# ugv_board.net
KiCad netlist of a schematic drawn in EAGLE
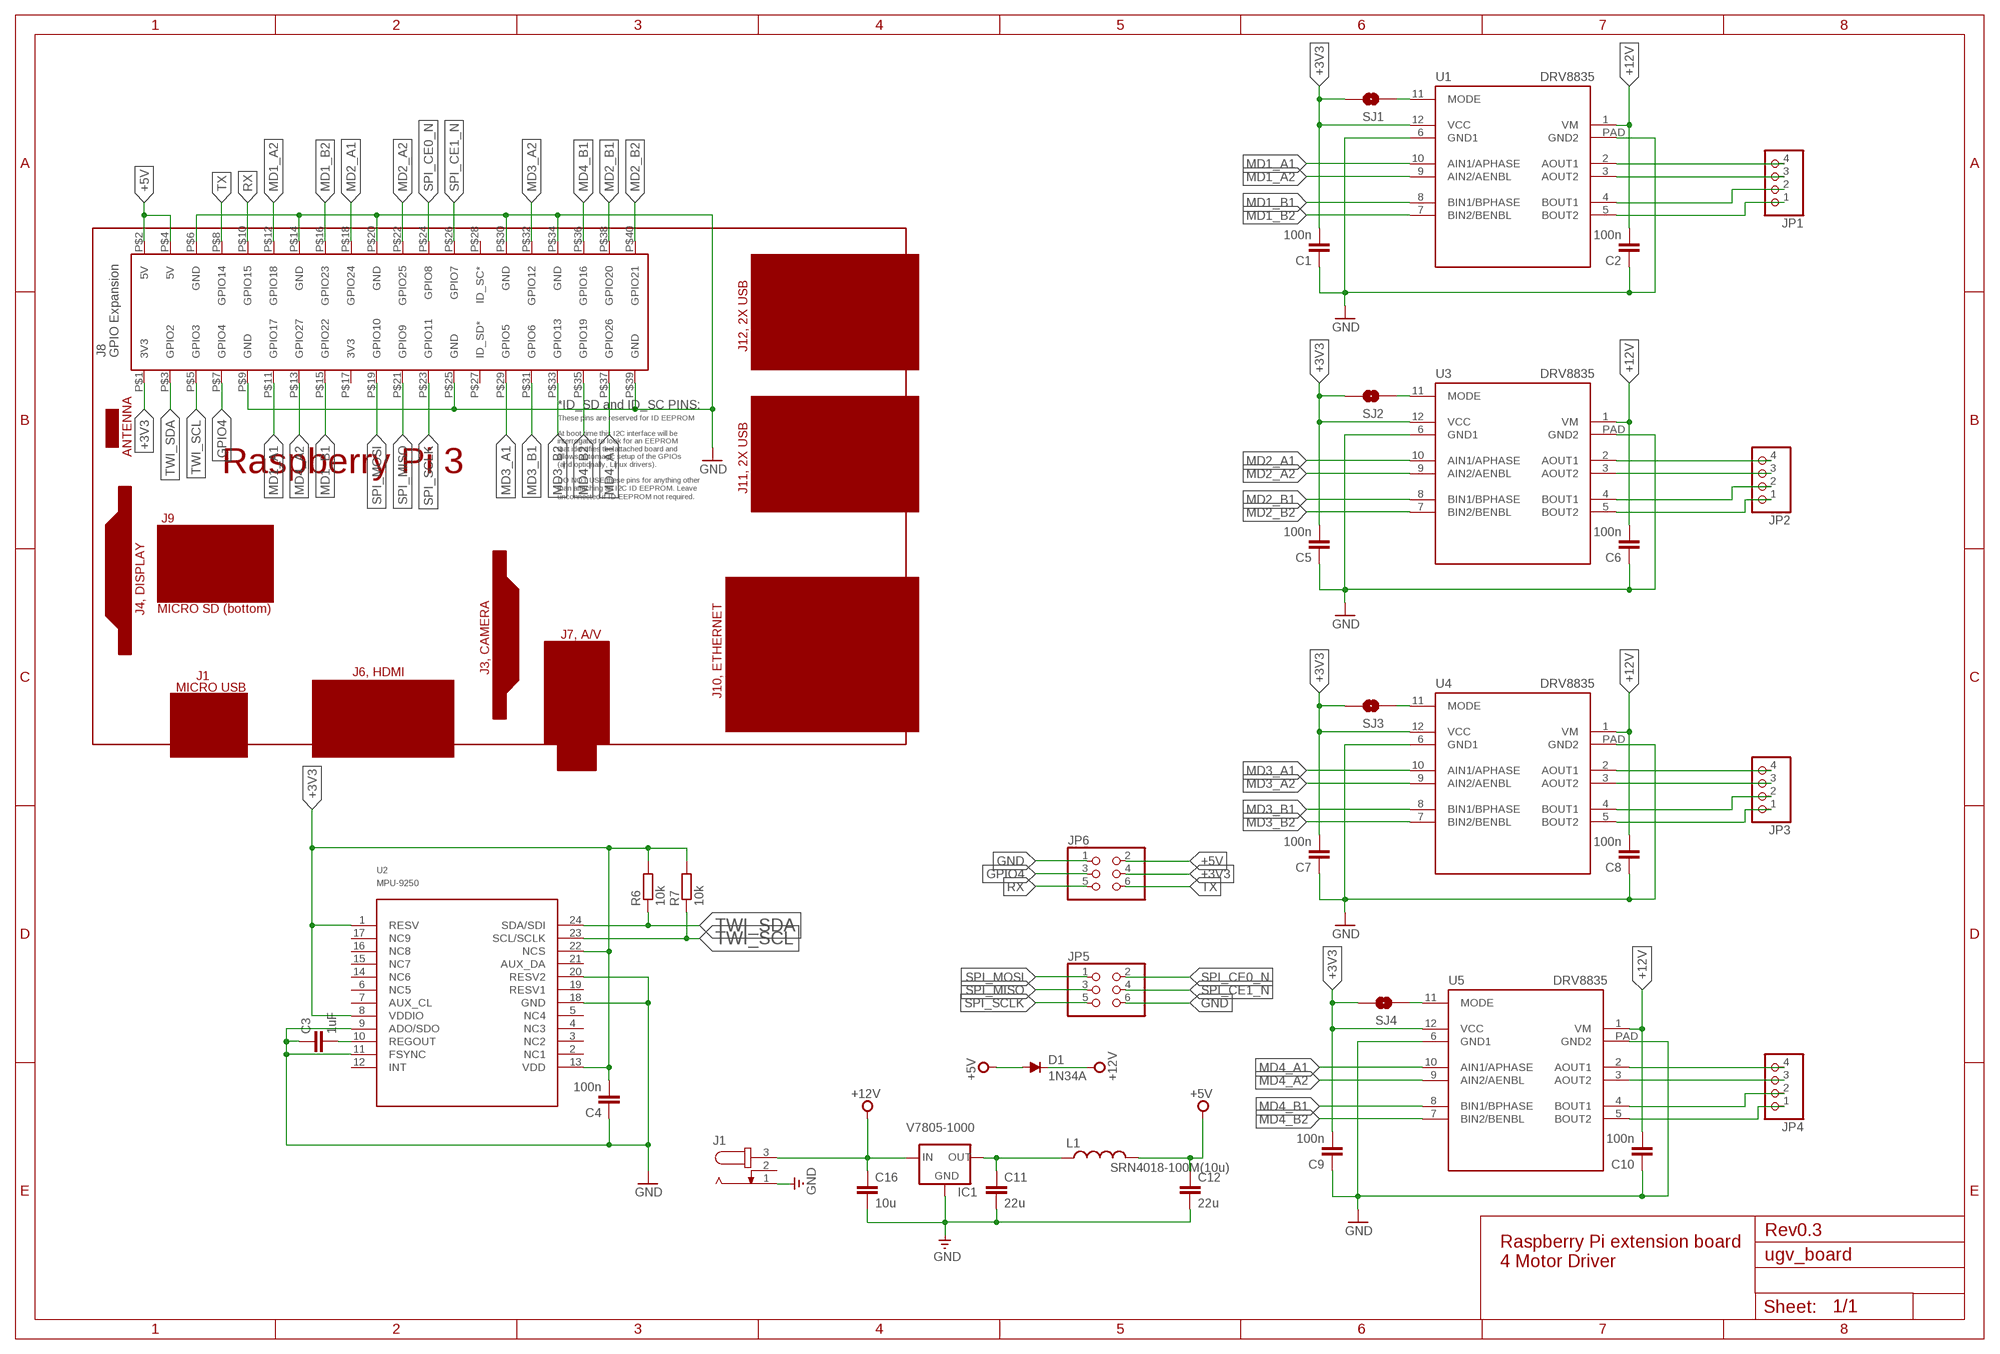
[diagram p0: schematic, sheet 1]

(export (version "E")
  (design (tool "Eeschema 10.0.6"))
  (components
    (comp (ref "C1")
      (value "100n")
      (footprint "eagle-import:C0402")
      (libsource (lib "eagle-import") (part "resistor_348_C-EUC0402"))
    )
    (comp (ref "C2")
      (value "100n")
      (footprint "eagle-import:C0402")
      (libsource (lib "eagle-import") (part "resistor_348_C-EUC0402"))
    )
    (comp (ref "C3")
      (value "1uF")
      (footprint "eagle-import:C0402")
      (libsource (lib "eagle-import") (part "resistor_348_C-EUC0402"))
    )
    (comp (ref "C4")
      (value "100n")
      (footprint "eagle-import:C0402")
      (libsource (lib "eagle-import") (part "resistor_348_C-EUC0402"))
    )
    (comp (ref "C5")
      (value "100n")
      (footprint "eagle-import:C0402")
      (libsource (lib "eagle-import") (part "resistor_348_C-EUC0402"))
    )
    (comp (ref "C6")
      (value "100n")
      (footprint "eagle-import:C0402")
      (libsource (lib "eagle-import") (part "resistor_348_C-EUC0402"))
    )
    (comp (ref "C7")
      (value "100n")
      (footprint "eagle-import:C0402")
      (libsource (lib "eagle-import") (part "resistor_348_C-EUC0402"))
    )
    (comp (ref "C8")
      (value "100n")
      (footprint "eagle-import:C0402")
      (libsource (lib "eagle-import") (part "resistor_348_C-EUC0402"))
    )
    (comp (ref "C9")
      (value "100n")
      (footprint "eagle-import:C0402")
      (libsource (lib "eagle-import") (part "resistor_348_C-EUC0402"))
    )
    (comp (ref "C10")
      (value "100n")
      (footprint "eagle-import:C0402")
      (libsource (lib "eagle-import") (part "resistor_348_C-EUC0402"))
    )
    (comp (ref "C11")
      (value "22u")
      (footprint "eagle-import:C0603")
      (libsource (lib "eagle-import") (part "C-EUC0603"))
    )
    (comp (ref "C12")
      (value "22u")
      (footprint "eagle-import:C0603")
      (libsource (lib "eagle-import") (part "C-EUC0603"))
    )
    (comp (ref "C16")
      (value "10u")
      (footprint "eagle-import:C0603")
      (libsource (lib "eagle-import") (part "C-EUC0603"))
    )
    (comp (ref "D1")
      (value "1N34A")
      (footprint "eagle-import:DO07")
      (libsource (lib "eagle-import") (part "1N34A"))
    )
    (comp (ref "IC1")
      (value "V7805-1000")
      (footprint "eagle-import:DIP_3PIN")
      (libsource (lib "eagle-import") (part "VR_1OUTXX"))
    )
    (comp (ref "J1")
      (value "JACK-PLUG0")
      (footprint "eagle-import:SPC4077")
      (libsource (lib "eagle-import") (part "JACK-PLUG0"))
    )
    (comp (ref "JP1")
      (value "PINHD-1X4M")
      (footprint "eagle-import:1X04M")
      (libsource (lib "eagle-import") (part "PINHD-1X4M"))
    )
    (comp (ref "JP2")
      (value "PINHD-1X4M")
      (footprint "eagle-import:1X04M")
      (libsource (lib "eagle-import") (part "PINHD-1X4M"))
    )
    (comp (ref "JP3")
      (value "PINHD-1X4M")
      (footprint "eagle-import:1X04M")
      (libsource (lib "eagle-import") (part "PINHD-1X4M"))
    )
    (comp (ref "JP4")
      (value "PINHD-1X4M")
      (footprint "eagle-import:1X04M")
      (libsource (lib "eagle-import") (part "PINHD-1X4M"))
    )
    (comp (ref "JP5")
      (value "PINHD-2X3")
      (footprint "eagle-import:2X03")
      (libsource (lib "eagle-import") (part "PINHD-2X3"))
    )
    (comp (ref "JP6")
      (value "PINHD-2X3")
      (footprint "eagle-import:2X03")
      (libsource (lib "eagle-import") (part "PINHD-2X3"))
    )
    (comp (ref "L1")
      (value "SRN4018-100M(10u)")
      (footprint "eagle-import:BOURNS-SRN4018")
      (libsource (lib "eagle-import") (part "BOURNS-SRN4018"))
    )
    (comp (ref "PCB1")
      (value "RPI3")
      (footprint "eagle-import:RPI3")
      (libsource (lib "eagle-import") (part "RPI3"))
    )
    (comp (ref "R6")
      (value "10k")
      (footprint "eagle-import:R0402")
      (libsource (lib "eagle-import") (part "R-EU_R0402"))
    )
    (comp (ref "R7")
      (value "10k")
      (footprint "eagle-import:R0402")
      (libsource (lib "eagle-import") (part "R-EU_R0402"))
    )
    (comp (ref "SJ1")
      (value "SOLDERJUMPERNC")
      (footprint "eagle-import:SJ_2S")
      (libsource (lib "eagle-import") (part "SOLDERJUMPERNC"))
    )
    (comp (ref "SJ2")
      (value "SOLDERJUMPERNC")
      (footprint "eagle-import:SJ_2S")
      (libsource (lib "eagle-import") (part "SOLDERJUMPERNC"))
    )
    (comp (ref "SJ3")
      (value "SOLDERJUMPERNC")
      (footprint "eagle-import:SJ_2S")
      (libsource (lib "eagle-import") (part "SOLDERJUMPERNC"))
    )
    (comp (ref "SJ4")
      (value "SOLDERJUMPERNC")
      (footprint "eagle-import:SJ_2S")
      (libsource (lib "eagle-import") (part "SOLDERJUMPERNC"))
    )
    (comp (ref "U1")
      (value "DRV8835")
      (footprint "eagle-import:WSON_2X3")
      (libsource (lib "eagle-import") (part "DRV8835"))
    )
    (comp (ref "U2")
      (value "MPU-9250")
      (footprint "eagle-import:LEAD-QFN24")
      (libsource (lib "eagle-import") (part "MPU-9250"))
    )
    (comp (ref "U3")
      (value "DRV8835")
      (footprint "eagle-import:WSON_2X3")
      (libsource (lib "eagle-import") (part "DRV8835"))
    )
    (comp (ref "U4")
      (value "DRV8835")
      (footprint "eagle-import:WSON_2X3")
      (libsource (lib "eagle-import") (part "DRV8835"))
    )
    (comp (ref "U5")
      (value "DRV8835")
      (footprint "eagle-import:WSON_2X3")
      (libsource (lib "eagle-import") (part "DRV8835"))
    )
  )
  (nets
    (net (code "1") (name "+3V3") (class "Default")
      (node (ref "C1") (pin "2") (pinfunction "2_2") (pintype "passive"))
      (node (ref "C4") (pin "2") (pinfunction "2_2") (pintype "passive"))
      (node (ref "C5") (pin "2") (pinfunction "2_2") (pintype "passive"))
      (node (ref "C7") (pin "2") (pinfunction "2_2") (pintype "passive"))
      (node (ref "C9") (pin "2") (pinfunction "2_2") (pintype "passive"))
      (node (ref "JP6") (pin "4") (pinfunction "4_4") (pintype "passive"))
      (node (ref "PCB1") (pin "P$1") (pinfunction "3V3_P$1") (pintype "bidirectional"))
      (node (ref "R6") (pin "2") (pinfunction "2_2") (pintype "passive"))
      (node (ref "R7") (pin "2") (pinfunction "2_2") (pintype "passive"))
      (node (ref "SJ1") (pin "2") (pinfunction "2_2") (pintype "passive"))
      (node (ref "SJ2") (pin "2") (pinfunction "2_2") (pintype "passive"))
      (node (ref "SJ3") (pin "2") (pinfunction "2_2") (pintype "passive"))
      (node (ref "SJ4") (pin "2") (pinfunction "2_2") (pintype "passive"))
      (node (ref "U1") (pin "12") (pinfunction "VCC_12") (pintype "bidirectional"))
      (node (ref "U2") (pin "1") (pinfunction "RESV_1") (pintype "bidirectional"))
      (node (ref "U2") (pin "13") (pinfunction "VDD_13") (pintype "bidirectional"))
      (node (ref "U2") (pin "22") (pinfunction "NCS_22") (pintype "bidirectional"))
      (node (ref "U2") (pin "8") (pinfunction "VDDIO_8") (pintype "bidirectional"))
      (node (ref "U3") (pin "12") (pinfunction "VCC_12") (pintype "bidirectional"))
      (node (ref "U4") (pin "12") (pinfunction "VCC_12") (pintype "bidirectional"))
      (node (ref "U5") (pin "12") (pinfunction "VCC_12") (pintype "bidirectional"))
    )
    (net (code "2") (name "+5V") (class "Default")
      (node (ref "C12") (pin "1") (pinfunction "1_1") (pintype "passive"))
      (node (ref "D1") (pin "A") (pinfunction "A_A") (pintype "passive"))
      (node (ref "JP6") (pin "2") (pinfunction "2_2") (pintype "passive"))
      (node (ref "L1") (pin "P$1") (pinfunction "1_P$1") (pintype "passive"))
      (node (ref "PCB1") (pin "P$2") (pinfunction "5V_P$2") (pintype "bidirectional"))
      (node (ref "PCB1") (pin "P$4") (pinfunction "5V_P$4") (pintype "bidirectional"))
    )
    (net (code "3") (name "+12V") (class "Default")
      (node (ref "C10") (pin "2") (pinfunction "2_2") (pintype "passive"))
      (node (ref "C16") (pin "1") (pinfunction "1_1") (pintype "passive"))
      (node (ref "C2") (pin "2") (pinfunction "2_2") (pintype "passive"))
      (node (ref "C6") (pin "2") (pinfunction "2_2") (pintype "passive"))
      (node (ref "C8") (pin "2") (pinfunction "2_2") (pintype "passive"))
      (node (ref "D1") (pin "C") (pinfunction "C_C") (pintype "passive"))
      (node (ref "IC1") (pin "IN") (pinfunction "IN_IN") (pintype "input"))
      (node (ref "J1") (pin "3") (pinfunction "3_3") (pintype "passive"))
      (node (ref "U1") (pin "1") (pinfunction "VM_1") (pintype "bidirectional"))
      (node (ref "U3") (pin "1") (pinfunction "VM_1") (pintype "bidirectional"))
      (node (ref "U4") (pin "1") (pinfunction "VM_1") (pintype "bidirectional"))
      (node (ref "U5") (pin "1") (pinfunction "VM_1") (pintype "bidirectional"))
    )
    (net (code "4") (name "GND") (class "Default")
      (node (ref "C1") (pin "1") (pinfunction "1_1") (pintype "passive"))
      (node (ref "C10") (pin "1") (pinfunction "1_1") (pintype "passive"))
      (node (ref "C11") (pin "2") (pinfunction "2_2") (pintype "passive"))
      (node (ref "C12") (pin "2") (pinfunction "2_2") (pintype "passive"))
      (node (ref "C16") (pin "2") (pinfunction "2_2") (pintype "passive"))
      (node (ref "C2") (pin "1") (pinfunction "1_1") (pintype "passive"))
      (node (ref "C3") (pin "1") (pinfunction "1_1") (pintype "passive"))
      (node (ref "C4") (pin "1") (pinfunction "1_1") (pintype "passive"))
      (node (ref "C5") (pin "1") (pinfunction "1_1") (pintype "passive"))
      (node (ref "C6") (pin "1") (pinfunction "1_1") (pintype "passive"))
      (node (ref "C7") (pin "1") (pinfunction "1_1") (pintype "passive"))
      (node (ref "C8") (pin "1") (pinfunction "1_1") (pintype "passive"))
      (node (ref "C9") (pin "1") (pinfunction "1_1") (pintype "passive"))
      (node (ref "IC1") (pin "GND") (pinfunction "GND_GND") (pintype "input"))
      (node (ref "J1") (pin "1") (pinfunction "1_1") (pintype "passive"))
      (node (ref "JP5") (pin "6") (pinfunction "6_6") (pintype "passive"))
      (node (ref "JP6") (pin "1") (pinfunction "1_1") (pintype "passive"))
      (node (ref "PCB1") (pin "P$14") (pinfunction "GND_P$14") (pintype "bidirectional"))
      (node (ref "PCB1") (pin "P$20") (pinfunction "GND_P$20") (pintype "bidirectional"))
      (node (ref "PCB1") (pin "P$25") (pinfunction "GND_P$25") (pintype "bidirectional"))
      (node (ref "PCB1") (pin "P$30") (pinfunction "GND_P$30") (pintype "bidirectional"))
      (node (ref "PCB1") (pin "P$34") (pinfunction "GND_P$34") (pintype "bidirectional"))
      (node (ref "PCB1") (pin "P$39") (pinfunction "GND_P$39") (pintype "bidirectional"))
      (node (ref "PCB1") (pin "P$6") (pinfunction "GND_P$6") (pintype "bidirectional"))
      (node (ref "PCB1") (pin "P$9") (pinfunction "GND_P$9") (pintype "bidirectional"))
      (node (ref "U1") (pin "6") (pinfunction "GND1_6") (pintype "bidirectional"))
      (node (ref "U1") (pin "PAD") (pinfunction "GND2_PAD") (pintype "bidirectional"))
      (node (ref "U2") (pin "11") (pinfunction "FSYNC_11") (pintype "bidirectional"))
      (node (ref "U2") (pin "18") (pinfunction "GND_18") (pintype "bidirectional"))
      (node (ref "U2") (pin "20") (pinfunction "RESV2_20") (pintype "bidirectional"))
      (node (ref "U2") (pin "9") (pinfunction "ADO/SDO_9") (pintype "bidirectional"))
      (node (ref "U3") (pin "6") (pinfunction "GND1_6") (pintype "bidirectional"))
      (node (ref "U3") (pin "PAD") (pinfunction "GND2_PAD") (pintype "bidirectional"))
      (node (ref "U4") (pin "6") (pinfunction "GND1_6") (pintype "bidirectional"))
      (node (ref "U4") (pin "PAD") (pinfunction "GND2_PAD") (pintype "bidirectional"))
      (node (ref "U5") (pin "6") (pinfunction "GND1_6") (pintype "bidirectional"))
      (node (ref "U5") (pin "PAD") (pinfunction "GND2_PAD") (pintype "bidirectional"))
    )
    (net (code "5") (name "GPIO4") (class "Default")
      (node (ref "JP6") (pin "3") (pinfunction "3_3") (pintype "passive"))
      (node (ref "PCB1") (pin "P$7") (pinfunction "GPIO4_P$7") (pintype "bidirectional"))
    )
    (net (code "6") (name "MD1_A1") (class "Default")
      (node (ref "PCB1") (pin "P$11") (pinfunction "GPIO17_P$11") (pintype "bidirectional"))
      (node (ref "U1") (pin "10") (pinfunction "AIN1/APHASE_10") (pintype "bidirectional"))
    )
    (net (code "7") (name "MD1_A2") (class "Default")
      (node (ref "PCB1") (pin "P$12") (pinfunction "GPIO18_P$12") (pintype "bidirectional"))
      (node (ref "U1") (pin "9") (pinfunction "AIN2/AENBL_9") (pintype "bidirectional"))
    )
    (net (code "8") (name "MD1_B1") (class "Default")
      (node (ref "PCB1") (pin "P$15") (pinfunction "GPIO22_P$15") (pintype "bidirectional"))
      (node (ref "U1") (pin "8") (pinfunction "BIN1/BPHASE_8") (pintype "bidirectional"))
    )
    (net (code "9") (name "MD1_B2") (class "Default")
      (node (ref "PCB1") (pin "P$16") (pinfunction "GPIO23_P$16") (pintype "bidirectional"))
      (node (ref "U1") (pin "7") (pinfunction "BIN2/BENBL_7") (pintype "bidirectional"))
    )
    (net (code "10") (name "MD2_A1") (class "Default")
      (node (ref "PCB1") (pin "P$18") (pinfunction "GPIO24_P$18") (pintype "bidirectional"))
      (node (ref "U3") (pin "10") (pinfunction "AIN1/APHASE_10") (pintype "bidirectional"))
    )
    (net (code "11") (name "MD2_A2") (class "Default")
      (node (ref "PCB1") (pin "P$22") (pinfunction "GPIO25_P$22") (pintype "bidirectional"))
      (node (ref "U3") (pin "9") (pinfunction "AIN2/AENBL_9") (pintype "bidirectional"))
    )
    (net (code "12") (name "MD2_B1") (class "Default")
      (node (ref "PCB1") (pin "P$38") (pinfunction "GPIO20_P$38") (pintype "bidirectional"))
      (node (ref "U3") (pin "8") (pinfunction "BIN1/BPHASE_8") (pintype "bidirectional"))
    )
    (net (code "13") (name "MD2_B2") (class "Default")
      (node (ref "PCB1") (pin "P$40") (pinfunction "GPIO21_P$40") (pintype "bidirectional"))
      (node (ref "U3") (pin "7") (pinfunction "BIN2/BENBL_7") (pintype "bidirectional"))
    )
    (net (code "14") (name "MD3_A1") (class "Default")
      (node (ref "PCB1") (pin "P$29") (pinfunction "GPIO5_P$29") (pintype "bidirectional"))
      (node (ref "U4") (pin "10") (pinfunction "AIN1/APHASE_10") (pintype "bidirectional"))
    )
    (net (code "15") (name "MD3_A2") (class "Default")
      (node (ref "PCB1") (pin "P$32") (pinfunction "GPIO12_P$32") (pintype "bidirectional"))
      (node (ref "U4") (pin "9") (pinfunction "AIN2/AENBL_9") (pintype "bidirectional"))
    )
    (net (code "16") (name "MD3_B1") (class "Default")
      (node (ref "PCB1") (pin "P$31") (pinfunction "GPIO6_P$31") (pintype "bidirectional"))
      (node (ref "U4") (pin "8") (pinfunction "BIN1/BPHASE_8") (pintype "bidirectional"))
    )
    (net (code "17") (name "MD3_B2") (class "Default")
      (node (ref "PCB1") (pin "P$33") (pinfunction "GPIO13_P$33") (pintype "bidirectional"))
      (node (ref "U4") (pin "7") (pinfunction "BIN2/BENBL_7") (pintype "bidirectional"))
    )
    (net (code "18") (name "MD4_A1") (class "Default")
      (node (ref "PCB1") (pin "P$37") (pinfunction "GPIO26_P$37") (pintype "bidirectional"))
      (node (ref "U5") (pin "10") (pinfunction "AIN1/APHASE_10") (pintype "bidirectional"))
    )
    (net (code "19") (name "MD4_A2") (class "Default")
      (node (ref "PCB1") (pin "P$13") (pinfunction "GPIO27_P$13") (pintype "bidirectional"))
      (node (ref "U5") (pin "9") (pinfunction "AIN2/AENBL_9") (pintype "bidirectional"))
    )
    (net (code "20") (name "MD4_B1") (class "Default")
      (node (ref "PCB1") (pin "P$36") (pinfunction "GPIO16_P$36") (pintype "bidirectional"))
      (node (ref "U5") (pin "8") (pinfunction "BIN1/BPHASE_8") (pintype "bidirectional"))
    )
    (net (code "21") (name "MD4_B2") (class "Default")
      (node (ref "PCB1") (pin "P$35") (pinfunction "GPIO19_P$35") (pintype "bidirectional"))
      (node (ref "U5") (pin "7") (pinfunction "BIN2/BENBL_7") (pintype "bidirectional"))
    )
    (net (code "22") (name "Net-(L1-2)") (class "Default")
      (node (ref "C11") (pin "1") (pinfunction "1_1") (pintype "passive"))
      (node (ref "IC1") (pin "OUT") (pinfunction "OUT_OUT") (pintype "passive"))
      (node (ref "L1") (pin "P$2") (pinfunction "2_P$2") (pintype "passive"))
    )
    (net (code "23") (name "Net-(U1-AOUT1)") (class "Default")
      (node (ref "JP1") (pin "4") (pinfunction "4_4") (pintype "passive"))
      (node (ref "U1") (pin "2") (pinfunction "AOUT1_2") (pintype "bidirectional"))
    )
    (net (code "24") (name "Net-(U1-AOUT2)") (class "Default")
      (node (ref "JP1") (pin "3") (pinfunction "3_3") (pintype "passive"))
      (node (ref "U1") (pin "3") (pinfunction "AOUT2_3") (pintype "bidirectional"))
    )
    (net (code "25") (name "Net-(U1-BOUT1)") (class "Default")
      (node (ref "JP1") (pin "2") (pinfunction "2_2") (pintype "passive"))
      (node (ref "U1") (pin "4") (pinfunction "BOUT1_4") (pintype "bidirectional"))
    )
    (net (code "26") (name "Net-(U1-BOUT2)") (class "Default")
      (node (ref "JP1") (pin "1") (pinfunction "1_1") (pintype "passive"))
      (node (ref "U1") (pin "5") (pinfunction "BOUT2_5") (pintype "bidirectional"))
    )
    (net (code "27") (name "Net-(U1-MODE)") (class "Default")
      (node (ref "SJ1") (pin "1") (pinfunction "1_1") (pintype "passive"))
      (node (ref "U1") (pin "11") (pinfunction "MODE_11") (pintype "bidirectional"))
    )
    (net (code "28") (name "Net-(U2-REGOUT)") (class "Default")
      (node (ref "C3") (pin "2") (pinfunction "2_2") (pintype "passive"))
      (node (ref "U2") (pin "10") (pinfunction "REGOUT_10") (pintype "bidirectional"))
    )
    (net (code "29") (name "Net-(U3-AOUT1)") (class "Default")
      (node (ref "JP2") (pin "4") (pinfunction "4_4") (pintype "passive"))
      (node (ref "U3") (pin "2") (pinfunction "AOUT1_2") (pintype "bidirectional"))
    )
    (net (code "30") (name "Net-(U3-AOUT2)") (class "Default")
      (node (ref "JP2") (pin "3") (pinfunction "3_3") (pintype "passive"))
      (node (ref "U3") (pin "3") (pinfunction "AOUT2_3") (pintype "bidirectional"))
    )
    (net (code "31") (name "Net-(U3-BOUT1)") (class "Default")
      (node (ref "JP2") (pin "2") (pinfunction "2_2") (pintype "passive"))
      (node (ref "U3") (pin "4") (pinfunction "BOUT1_4") (pintype "bidirectional"))
    )
    (net (code "32") (name "Net-(U3-BOUT2)") (class "Default")
      (node (ref "JP2") (pin "1") (pinfunction "1_1") (pintype "passive"))
      (node (ref "U3") (pin "5") (pinfunction "BOUT2_5") (pintype "bidirectional"))
    )
    (net (code "33") (name "Net-(U3-MODE)") (class "Default")
      (node (ref "SJ2") (pin "1") (pinfunction "1_1") (pintype "passive"))
      (node (ref "U3") (pin "11") (pinfunction "MODE_11") (pintype "bidirectional"))
    )
    (net (code "34") (name "Net-(U4-AOUT1)") (class "Default")
      (node (ref "JP3") (pin "4") (pinfunction "4_4") (pintype "passive"))
      (node (ref "U4") (pin "2") (pinfunction "AOUT1_2") (pintype "bidirectional"))
    )
    (net (code "35") (name "Net-(U4-AOUT2)") (class "Default")
      (node (ref "JP3") (pin "3") (pinfunction "3_3") (pintype "passive"))
      (node (ref "U4") (pin "3") (pinfunction "AOUT2_3") (pintype "bidirectional"))
    )
    (net (code "36") (name "Net-(U4-BOUT1)") (class "Default")
      (node (ref "JP3") (pin "2") (pinfunction "2_2") (pintype "passive"))
      (node (ref "U4") (pin "4") (pinfunction "BOUT1_4") (pintype "bidirectional"))
    )
    (net (code "37") (name "Net-(U4-BOUT2)") (class "Default")
      (node (ref "JP3") (pin "1") (pinfunction "1_1") (pintype "passive"))
      (node (ref "U4") (pin "5") (pinfunction "BOUT2_5") (pintype "bidirectional"))
    )
    (net (code "38") (name "Net-(U4-MODE)") (class "Default")
      (node (ref "SJ3") (pin "1") (pinfunction "1_1") (pintype "passive"))
      (node (ref "U4") (pin "11") (pinfunction "MODE_11") (pintype "bidirectional"))
    )
    (net (code "39") (name "Net-(U5-AOUT1)") (class "Default")
      (node (ref "JP4") (pin "4") (pinfunction "4_4") (pintype "passive"))
      (node (ref "U5") (pin "2") (pinfunction "AOUT1_2") (pintype "bidirectional"))
    )
    (net (code "40") (name "Net-(U5-AOUT2)") (class "Default")
      (node (ref "JP4") (pin "3") (pinfunction "3_3") (pintype "passive"))
      (node (ref "U5") (pin "3") (pinfunction "AOUT2_3") (pintype "bidirectional"))
    )
    (net (code "41") (name "Net-(U5-BOUT1)") (class "Default")
      (node (ref "JP4") (pin "2") (pinfunction "2_2") (pintype "passive"))
      (node (ref "U5") (pin "4") (pinfunction "BOUT1_4") (pintype "bidirectional"))
    )
    (net (code "42") (name "Net-(U5-BOUT2)") (class "Default")
      (node (ref "JP4") (pin "1") (pinfunction "1_1") (pintype "passive"))
      (node (ref "U5") (pin "5") (pinfunction "BOUT2_5") (pintype "bidirectional"))
    )
    (net (code "43") (name "Net-(U5-MODE)") (class "Default")
      (node (ref "SJ4") (pin "1") (pinfunction "1_1") (pintype "passive"))
      (node (ref "U5") (pin "11") (pinfunction "MODE_11") (pintype "bidirectional"))
    )
    (net (code "44") (name "RX") (class "Default")
      (node (ref "JP6") (pin "5") (pinfunction "5_5") (pintype "passive"))
      (node (ref "PCB1") (pin "P$10") (pinfunction "GPIO15_P$10") (pintype "bidirectional"))
    )
    (net (code "45") (name "SPI_CE0_N") (class "Default")
      (node (ref "JP5") (pin "2") (pinfunction "2_2") (pintype "passive"))
      (node (ref "PCB1") (pin "P$24") (pinfunction "GPIO8_P$24") (pintype "bidirectional"))
    )
    (net (code "46") (name "SPI_CE1_N") (class "Default")
      (node (ref "JP5") (pin "4") (pinfunction "4_4") (pintype "passive"))
      (node (ref "PCB1") (pin "P$26") (pinfunction "GPIO7_P$26") (pintype "bidirectional"))
    )
    (net (code "47") (name "SPI_MISO") (class "Default")
      (node (ref "JP5") (pin "3") (pinfunction "3_3") (pintype "passive"))
      (node (ref "PCB1") (pin "P$21") (pinfunction "GPIO9_P$21") (pintype "bidirectional"))
    )
    (net (code "48") (name "SPI_MOSI") (class "Default")
      (node (ref "JP5") (pin "1") (pinfunction "1_1") (pintype "passive"))
      (node (ref "PCB1") (pin "P$19") (pinfunction "GPIO10_P$19") (pintype "bidirectional"))
    )
    (net (code "49") (name "SPI_SCLK") (class "Default")
      (node (ref "JP5") (pin "5") (pinfunction "5_5") (pintype "passive"))
      (node (ref "PCB1") (pin "P$23") (pinfunction "GPIO11_P$23") (pintype "bidirectional"))
    )
    (net (code "50") (name "TWI_SCL") (class "Default")
      (node (ref "PCB1") (pin "P$5") (pinfunction "GPIO3_P$5") (pintype "bidirectional"))
      (node (ref "R7") (pin "1") (pinfunction "1_1") (pintype "passive"))
      (node (ref "U2") (pin "23") (pinfunction "SCL/SCLK_23") (pintype "bidirectional"))
    )
    (net (code "51") (name "TWI_SDA") (class "Default")
      (node (ref "PCB1") (pin "P$3") (pinfunction "GPIO2_P$3") (pintype "bidirectional"))
      (node (ref "R6") (pin "1") (pinfunction "1_1") (pintype "passive"))
      (node (ref "U2") (pin "24") (pinfunction "SDA/SDI_24") (pintype "bidirectional"))
    )
    (net (code "52") (name "TX") (class "Default")
      (node (ref "JP6") (pin "6") (pinfunction "6_6") (pintype "passive"))
      (node (ref "PCB1") (pin "P$8") (pinfunction "GPIO14_P$8") (pintype "bidirectional"))
    )
    (net (code "53") (name "unconnected-(J1-Pad2)") (class "Default")
      (node (ref "J1") (pin "2") (pinfunction "2_2") (pintype "passive"))
    )
    (net (code "54") (name "unconnected-(PCB1-3V3-PadP$17)") (class "Default")
      (node (ref "PCB1") (pin "P$17") (pinfunction "3V3_P$17") (pintype "bidirectional"))
    )
    (net (code "55") (name "unconnected-(PCB1-ID_SC*-PadP$28)") (class "Default")
      (node (ref "PCB1") (pin "P$28") (pinfunction "ID_SC*_P$28") (pintype "bidirectional"))
    )
    (net (code "56") (name "unconnected-(PCB1-ID_SD*-PadP$27)") (class "Default")
      (node (ref "PCB1") (pin "P$27") (pinfunction "ID_SD*_P$27") (pintype "bidirectional"))
    )
    (net (code "57") (name "unconnected-(U2-AUX_CL-Pad7)") (class "Default")
      (node (ref "U2") (pin "7") (pinfunction "AUX_CL_7") (pintype "bidirectional"))
    )
    (net (code "58") (name "unconnected-(U2-AUX_DA-Pad21)") (class "Default")
      (node (ref "U2") (pin "21") (pinfunction "AUX_DA_21") (pintype "bidirectional"))
    )
    (net (code "59") (name "unconnected-(U2-INT-Pad12)") (class "Default")
      (node (ref "U2") (pin "12") (pinfunction "INT_12") (pintype "bidirectional"))
    )
    (net (code "60") (name "unconnected-(U2-NC1-Pad2)") (class "Default")
      (node (ref "U2") (pin "2") (pinfunction "NC1_2") (pintype "bidirectional"))
    )
    (net (code "61") (name "unconnected-(U2-NC2-Pad3)") (class "Default")
      (node (ref "U2") (pin "3") (pinfunction "NC2_3") (pintype "bidirectional"))
    )
    (net (code "62") (name "unconnected-(U2-NC3-Pad4)") (class "Default")
      (node (ref "U2") (pin "4") (pinfunction "NC3_4") (pintype "bidirectional"))
    )
    (net (code "63") (name "unconnected-(U2-NC4-Pad5)") (class "Default")
      (node (ref "U2") (pin "5") (pinfunction "NC4_5") (pintype "bidirectional"))
    )
    (net (code "64") (name "unconnected-(U2-NC5-Pad6)") (class "Default")
      (node (ref "U2") (pin "6") (pinfunction "NC5_6") (pintype "bidirectional"))
    )
    (net (code "65") (name "unconnected-(U2-NC6-Pad14)") (class "Default")
      (node (ref "U2") (pin "14") (pinfunction "NC6_14") (pintype "bidirectional"))
    )
    (net (code "66") (name "unconnected-(U2-NC7-Pad15)") (class "Default")
      (node (ref "U2") (pin "15") (pinfunction "NC7_15") (pintype "bidirectional"))
    )
    (net (code "67") (name "unconnected-(U2-NC8-Pad16)") (class "Default")
      (node (ref "U2") (pin "16") (pinfunction "NC8_16") (pintype "bidirectional"))
    )
    (net (code "68") (name "unconnected-(U2-NC9-Pad17)") (class "Default")
      (node (ref "U2") (pin "17") (pinfunction "NC9_17") (pintype "bidirectional"))
    )
    (net (code "69") (name "unconnected-(U2-RESV1-Pad19)") (class "Default")
      (node (ref "U2") (pin "19") (pinfunction "RESV1_19") (pintype "bidirectional"))
    )
  )
)
